# feeder_microcontroller_side.net
KiCad netlist of a schematic drawn in EAGLE
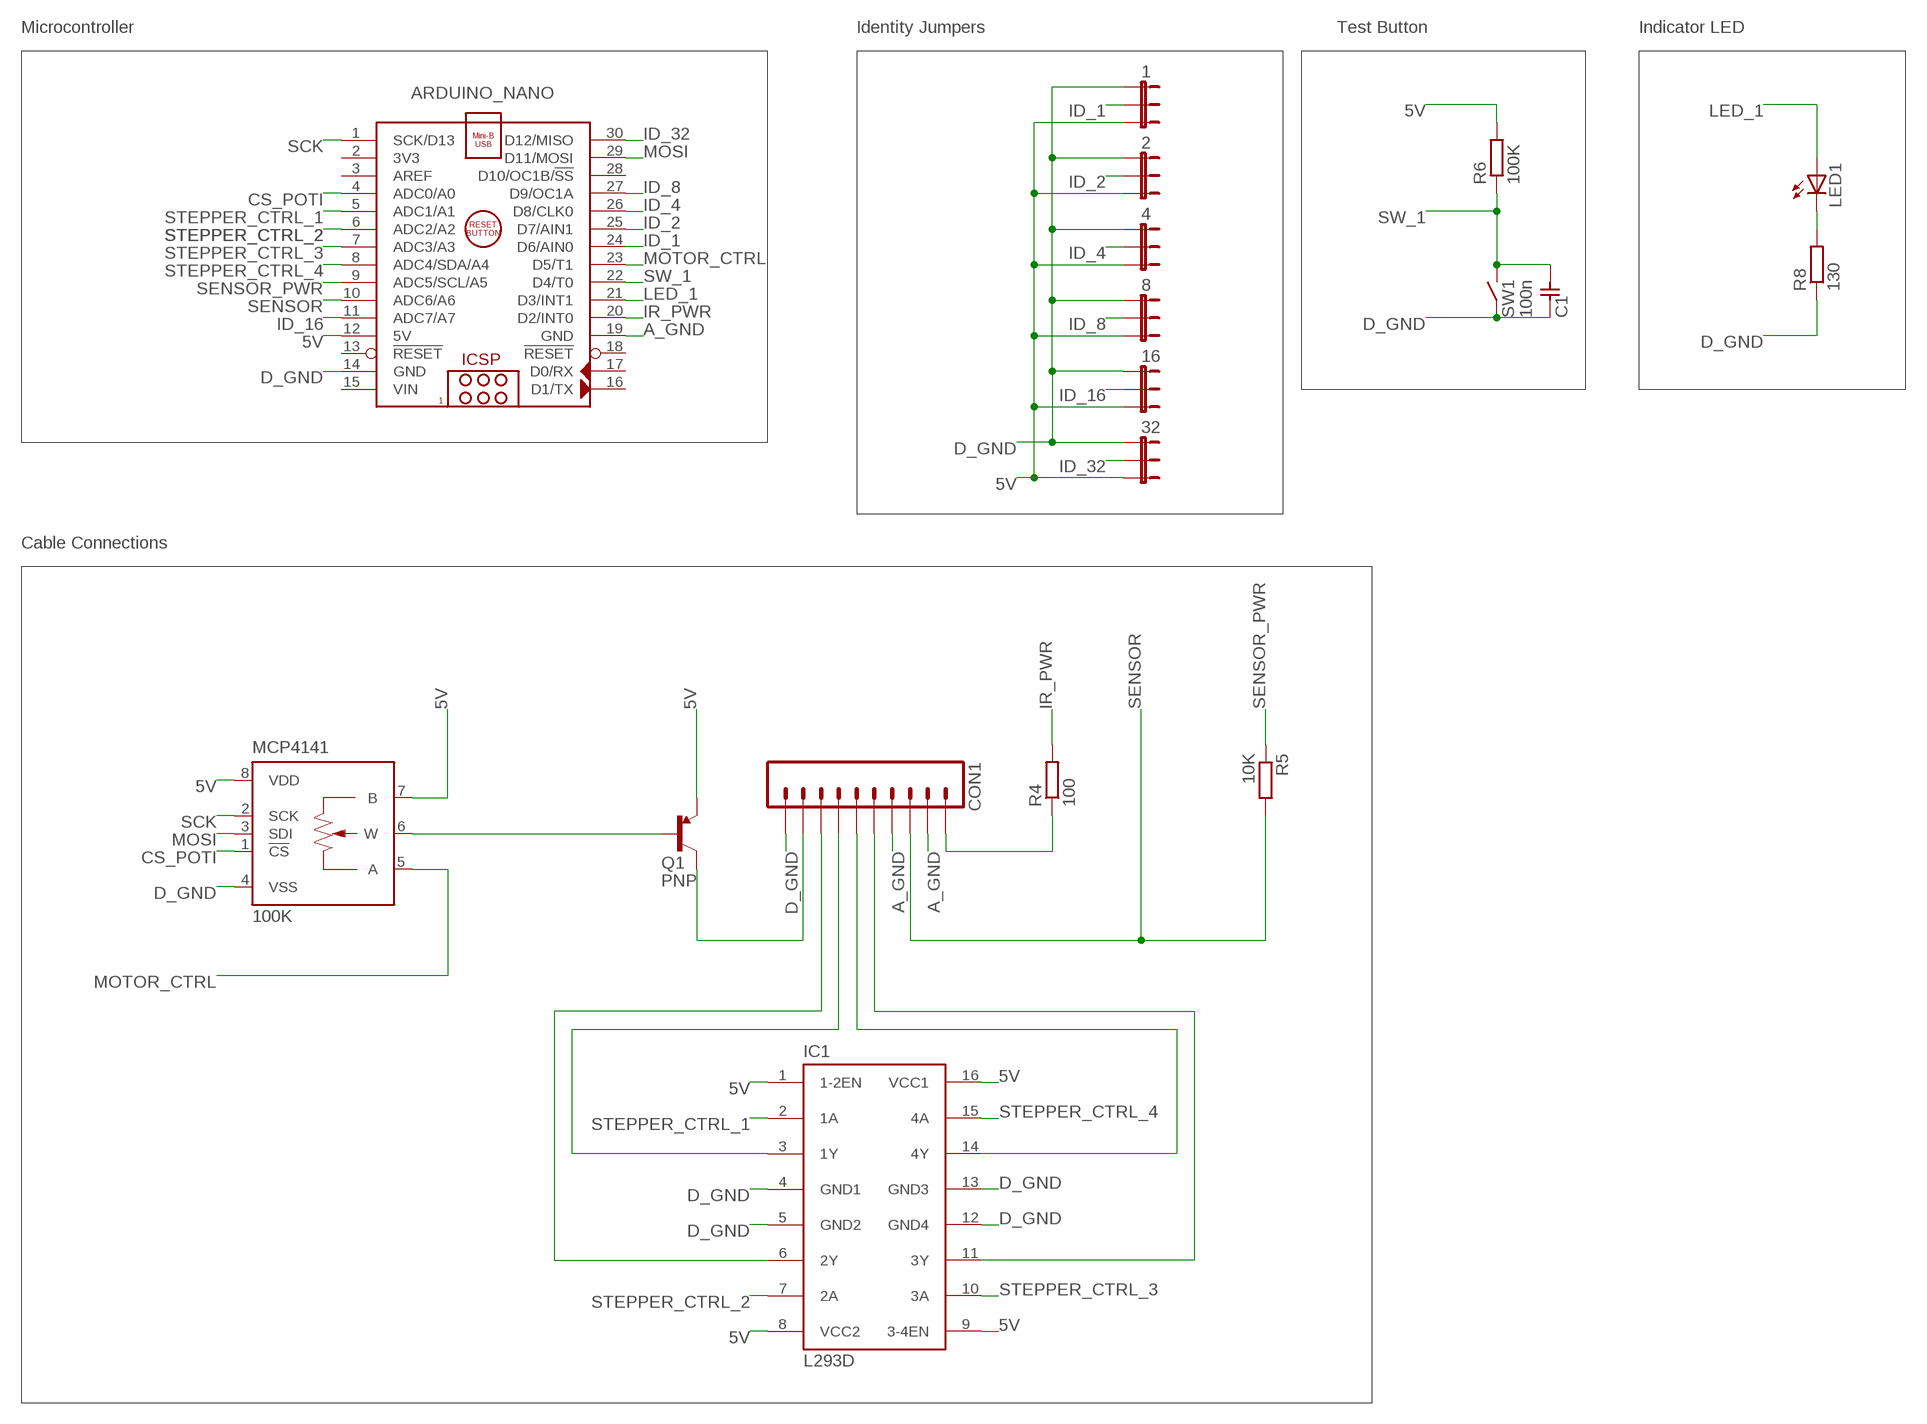
[diagram p0: schematic, sheet 1]

(export (version "E")
  (design (tool "Eeschema 10.0.6"))
  (components
    (comp (ref "1")
      (value "JP2E")
      (footprint "eagle-import:JP2")
      (libsource (lib "eagle-import") (part "JP2E"))
    )
    (comp (ref "2")
      (value "JP2E")
      (footprint "eagle-import:JP2")
      (libsource (lib "eagle-import") (part "JP2E"))
    )
    (comp (ref "4")
      (value "JP2E")
      (footprint "eagle-import:JP2")
      (libsource (lib "eagle-import") (part "JP2E"))
    )
    (comp (ref "8")
      (value "JP2E")
      (footprint "eagle-import:JP2")
      (libsource (lib "eagle-import") (part "JP2E"))
    )
    (comp (ref "16")
      (value "JP2E")
      (footprint "eagle-import:JP2")
      (libsource (lib "eagle-import") (part "JP2E"))
    )
    (comp (ref "32")
      (value "JP2E")
      (footprint "eagle-import:JP2")
      (libsource (lib "eagle-import") (part "JP2E"))
    )
    (comp (ref "ARDUINO_NANO")
      (value "ARDUINO_NANO")
      (footprint "eagle-import:ARDUINO_NANO")
      (libsource (lib "eagle-import") (part "ARDUINO_NANO"))
    )
    (comp (ref "C1")
      (value "100n")
      (footprint "eagle-import:CAPACITOR")
      (libsource (lib "eagle-import") (part "CAPACITOR"))
    )
    (comp (ref "CON1")
      (value "CON_10")
      (footprint "eagle-import:CON_10P_1.25_ALIEXPRESS")
      (libsource (lib "eagle-import") (part "CON_10"))
    )
    (comp (ref "IC1")
      (value "L293D")
      (footprint "eagle-import:DIL16")
      (libsource (lib "eagle-import") (part "L293D"))
    )
    (comp (ref "LED1")
      (value "LED_3MM")
      (footprint "eagle-import:TCR5000_IR_EMITTER")
      (libsource (lib "eagle-import") (part "LED_3MM"))
    )
    (comp (ref "MCP4141")
      (value "100K")
      (footprint "eagle-import:DIL08")
      (libsource (lib "eagle-import") (part "MCP_41X1_DIGI_POT"))
    )
    (comp (ref "Q1")
      (value "PNP")
      (footprint "eagle-import:TO92-")
      (libsource (lib "eagle-import") (part "PNP"))
    )
    (comp (ref "R4")
      (value "100")
      (footprint "eagle-import:0204_7")
      (libsource (lib "eagle-import") (part "R-EU_0204/7"))
    )
    (comp (ref "R5")
      (value "10K")
      (footprint "eagle-import:0204_7")
      (libsource (lib "eagle-import") (part "R-EU_0204/7"))
    )
    (comp (ref "R6")
      (value "100K")
      (footprint "eagle-import:0204_7")
      (libsource (lib "eagle-import") (part "R-EU_0204/7"))
    )
    (comp (ref "R8")
      (value "130")
      (footprint "eagle-import:0204_7")
      (libsource (lib "eagle-import") (part "R-EU_0204/7"))
    )
    (comp (ref "SW1")
      (value "BUTTON")
      (footprint "eagle-import:KS-01Q-01_BUTTON")
      (libsource (lib "eagle-import") (part "BUTTON"))
    )
  )
  (nets
    (net (code "1") (name "/5V") (class "Default")
      (node (ref "1") (pin "3") (pinfunction "3_3") (pintype "passive"))
      (node (ref "16") (pin "3") (pinfunction "3_3") (pintype "passive"))
      (node (ref "2") (pin "3") (pinfunction "3_3") (pintype "passive"))
      (node (ref "32") (pin "3") (pinfunction "3_3") (pintype "passive"))
      (node (ref "4") (pin "3") (pinfunction "3_3") (pintype "passive"))
      (node (ref "8") (pin "3") (pinfunction "3_3") (pintype "passive"))
      (node (ref "ARDUINO_NANO") (pin "12") (pinfunction "5V_12") (pintype "power_in"))
      (node (ref "IC1") (pin "1") (pinfunction "1-2EN_1") (pintype "input"))
      (node (ref "IC1") (pin "16") (pinfunction "VCC1_16") (pintype "power_in"))
      (node (ref "IC1") (pin "8") (pinfunction "VCC2_8") (pintype "power_in"))
      (node (ref "IC1") (pin "9") (pinfunction "3-4EN_9") (pintype "input"))
      (node (ref "MCP4141") (pin "7") (pinfunction "B_7") (pintype "passive"))
      (node (ref "MCP4141") (pin "8") (pinfunction "VDD_8") (pintype "power_in"))
      (node (ref "Q1") (pin "E") (pinfunction "E_E") (pintype "passive"))
      (node (ref "R6") (pin "2") (pinfunction "2_2") (pintype "passive"))
    )
    (net (code "2") (name "/A_GND") (class "Default")
      (node (ref "ARDUINO_NANO") (pin "19") (pinfunction "GND_19") (pintype "power_in"))
      (node (ref "CON1") (pin "2") (pinfunction "2_2") (pintype "passive"))
      (node (ref "CON1") (pin "4") (pinfunction "4_4") (pintype "passive"))
    )
    (net (code "3") (name "/CS_POTI") (class "Default")
      (node (ref "ARDUINO_NANO") (pin "4") (pinfunction "ADC0/A0_4") (pintype "bidirectional"))
      (node (ref "MCP4141") (pin "1") (pinfunction "~{CS}_1") (pintype "input"))
    )
    (net (code "4") (name "/D_GND") (class "Default")
      (node (ref "1") (pin "1") (pinfunction "1_1") (pintype "passive"))
      (node (ref "16") (pin "1") (pinfunction "1_1") (pintype "passive"))
      (node (ref "2") (pin "1") (pinfunction "1_1") (pintype "passive"))
      (node (ref "32") (pin "1") (pinfunction "1_1") (pintype "passive"))
      (node (ref "4") (pin "1") (pinfunction "1_1") (pintype "passive"))
      (node (ref "8") (pin "1") (pinfunction "1_1") (pintype "passive"))
      (node (ref "ARDUINO_NANO") (pin "14") (pinfunction "GND_14") (pintype "power_in"))
      (node (ref "C1") (pin "P$1") (pinfunction "1_P$1") (pintype "passive"))
      (node (ref "CON1") (pin "10") (pinfunction "10_10") (pintype "passive"))
      (node (ref "IC1") (pin "12") (pinfunction "GND4_12") (pintype "power_in"))
      (node (ref "IC1") (pin "13") (pinfunction "GND3_13") (pintype "power_in"))
      (node (ref "IC1") (pin "4") (pinfunction "GND1_4") (pintype "power_in"))
      (node (ref "IC1") (pin "5") (pinfunction "GND2_5") (pintype "power_in"))
      (node (ref "MCP4141") (pin "4") (pinfunction "VSS_4") (pintype "power_in"))
      (node (ref "R8") (pin "1") (pinfunction "1_1") (pintype "passive"))
      (node (ref "SW1") (pin "1") (pinfunction "1_1") (pintype "passive"))
      (node (ref "SW1") (pin "3") (pinfunction "1_3") (pintype "passive"))
    )
    (net (code "5") (name "/ID_1") (class "Default")
      (node (ref "1") (pin "2") (pinfunction "2_2") (pintype "passive"))
      (node (ref "ARDUINO_NANO") (pin "24") (pinfunction "D6/AIN0_24") (pintype "bidirectional"))
    )
    (net (code "6") (name "/ID_2") (class "Default")
      (node (ref "2") (pin "2") (pinfunction "2_2") (pintype "passive"))
      (node (ref "ARDUINO_NANO") (pin "25") (pinfunction "D7/AIN1_25") (pintype "bidirectional"))
    )
    (net (code "7") (name "/ID_4") (class "Default")
      (node (ref "4") (pin "2") (pinfunction "2_2") (pintype "passive"))
      (node (ref "ARDUINO_NANO") (pin "26") (pinfunction "D8/CLK0_26") (pintype "bidirectional"))
    )
    (net (code "8") (name "/ID_8") (class "Default")
      (node (ref "8") (pin "2") (pinfunction "2_2") (pintype "passive"))
      (node (ref "ARDUINO_NANO") (pin "27") (pinfunction "D9/OC1A_27") (pintype "bidirectional"))
    )
    (net (code "9") (name "/ID_16") (class "Default")
      (node (ref "16") (pin "2") (pinfunction "2_2") (pintype "passive"))
      (node (ref "ARDUINO_NANO") (pin "11") (pinfunction "ADC7/A7_11") (pintype "bidirectional"))
    )
    (net (code "10") (name "/ID_32") (class "Default")
      (node (ref "32") (pin "2") (pinfunction "2_2") (pintype "passive"))
      (node (ref "ARDUINO_NANO") (pin "30") (pinfunction "D12/MISO_30") (pintype "bidirectional"))
    )
    (net (code "11") (name "/IR_PWR") (class "Default")
      (node (ref "ARDUINO_NANO") (pin "20") (pinfunction "D2/INT0_20") (pintype "bidirectional"))
      (node (ref "R4") (pin "2") (pinfunction "2_2") (pintype "passive"))
    )
    (net (code "12") (name "/LED_1") (class "Default")
      (node (ref "ARDUINO_NANO") (pin "21") (pinfunction "D3/INT1_21") (pintype "bidirectional"))
      (node (ref "LED1") (pin "A") (pinfunction "A_A") (pintype "passive"))
    )
    (net (code "13") (name "/MOSI") (class "Default")
      (node (ref "ARDUINO_NANO") (pin "29") (pinfunction "D11/MOSI_29") (pintype "bidirectional"))
      (node (ref "MCP4141") (pin "3") (pinfunction "SDI_3") (pintype "input"))
    )
    (net (code "14") (name "/MOTOR_CTRL") (class "Default")
      (node (ref "ARDUINO_NANO") (pin "23") (pinfunction "D5/T1_23") (pintype "bidirectional"))
      (node (ref "MCP4141") (pin "5") (pinfunction "A_5") (pintype "passive"))
    )
    (net (code "15") (name "/SCK") (class "Default")
      (node (ref "ARDUINO_NANO") (pin "1") (pinfunction "SCK/D13_1") (pintype "bidirectional"))
      (node (ref "MCP4141") (pin "2") (pinfunction "SCK_2") (pintype "input"))
    )
    (net (code "16") (name "/SENSOR") (class "Default")
      (node (ref "ARDUINO_NANO") (pin "10") (pinfunction "ADC6/A6_10") (pintype "bidirectional"))
      (node (ref "CON1") (pin "3") (pinfunction "3_3") (pintype "passive"))
      (node (ref "R5") (pin "2") (pinfunction "2_2") (pintype "passive"))
    )
    (net (code "17") (name "/SENSOR_PWR") (class "Default")
      (node (ref "ARDUINO_NANO") (pin "9") (pinfunction "ADC5/SCL/A5_9") (pintype "bidirectional"))
      (node (ref "R5") (pin "1") (pinfunction "1_1") (pintype "passive"))
    )
    (net (code "18") (name "/STEPPER_CTRL_1") (class "Default")
      (node (ref "ARDUINO_NANO") (pin "5") (pinfunction "ADC1/A1_5") (pintype "bidirectional"))
      (node (ref "IC1") (pin "2") (pinfunction "1A_2") (pintype "input"))
    )
    (net (code "19") (name "/STEPPER_CTRL_2") (class "Default")
      (node (ref "ARDUINO_NANO") (pin "6") (pinfunction "ADC2/A2_6") (pintype "bidirectional"))
      (node (ref "IC1") (pin "7") (pinfunction "2A_7") (pintype "input"))
    )
    (net (code "20") (name "/STEPPER_CTRL_3") (class "Default")
      (node (ref "ARDUINO_NANO") (pin "7") (pinfunction "ADC3/A3_7") (pintype "bidirectional"))
      (node (ref "IC1") (pin "10") (pinfunction "3A_10") (pintype "input"))
    )
    (net (code "21") (name "/STEPPER_CTRL_4") (class "Default")
      (node (ref "ARDUINO_NANO") (pin "8") (pinfunction "ADC4/SDA/A4_8") (pintype "bidirectional"))
      (node (ref "IC1") (pin "15") (pinfunction "4A_15") (pintype "input"))
    )
    (net (code "22") (name "/SW_1") (class "Default")
      (node (ref "ARDUINO_NANO") (pin "22") (pinfunction "D4/T0_22") (pintype "bidirectional"))
      (node (ref "C1") (pin "P$2") (pinfunction "2_P$2") (pintype "passive"))
      (node (ref "R6") (pin "1") (pinfunction "1_1") (pintype "passive"))
      (node (ref "SW1") (pin "2") (pinfunction "2_2") (pintype "passive"))
      (node (ref "SW1") (pin "4") (pinfunction "2_4") (pintype "passive"))
    )
    (net (code "23") (name "/VIN") (class "Default")
      (node (ref "ARDUINO_NANO") (pin "15") (pinfunction "VIN_15") (pintype "power_in"))
    )
    (net (code "24") (name "Net-(CON1-Pad1)") (class "Default")
      (node (ref "CON1") (pin "1") (pinfunction "1_1") (pintype "passive"))
      (node (ref "R4") (pin "1") (pinfunction "1_1") (pintype "passive"))
    )
    (net (code "25") (name "Net-(CON1-Pad9)") (class "Default")
      (node (ref "CON1") (pin "9") (pinfunction "9_9") (pintype "passive"))
      (node (ref "Q1") (pin "C") (pinfunction "C_C") (pintype "passive"))
    )
    (net (code "26") (name "Net-(IC1-1Y)") (class "Default")
      (node (ref "CON1") (pin "7") (pinfunction "7_7") (pintype "passive"))
      (node (ref "IC1") (pin "3") (pinfunction "1Y_3") (pintype "output"))
    )
    (net (code "27") (name "Net-(IC1-2Y)") (class "Default")
      (node (ref "CON1") (pin "8") (pinfunction "8_8") (pintype "passive"))
      (node (ref "IC1") (pin "6") (pinfunction "2Y_6") (pintype "output"))
    )
    (net (code "28") (name "Net-(IC1-3Y)") (class "Default")
      (node (ref "CON1") (pin "5") (pinfunction "5_5") (pintype "passive"))
      (node (ref "IC1") (pin "11") (pinfunction "3Y_11") (pintype "output"))
    )
    (net (code "29") (name "Net-(IC1-4Y)") (class "Default")
      (node (ref "CON1") (pin "6") (pinfunction "6_6") (pintype "passive"))
      (node (ref "IC1") (pin "14") (pinfunction "4Y_14") (pintype "output"))
    )
    (net (code "30") (name "Net-(LED1-PadC)") (class "Default")
      (node (ref "LED1") (pin "C") (pinfunction "C_C") (pintype "passive"))
      (node (ref "R8") (pin "2") (pinfunction "2_2") (pintype "passive"))
    )
    (net (code "31") (name "Net-(MCP4141-W)") (class "Default")
      (node (ref "MCP4141") (pin "6") (pinfunction "W_6") (pintype "passive"))
      (node (ref "Q1") (pin "B") (pinfunction "B_B") (pintype "passive"))
    )
    (net (code "32") (name "unconnected-(ARDUINO_NANO-3V3-Pad2)") (class "Default")
      (node (ref "ARDUINO_NANO") (pin "2") (pinfunction "3V3_2") (pintype "output"))
    )
    (net (code "33") (name "unconnected-(ARDUINO_NANO-AREF-Pad3)") (class "Default")
      (node (ref "ARDUINO_NANO") (pin "3") (pinfunction "AREF_3") (pintype "input"))
    )
    (net (code "34") (name "unconnected-(ARDUINO_NANO-D0{slash}RX-Pad17)") (class "Default")
      (node (ref "ARDUINO_NANO") (pin "17") (pinfunction "D0/RX_17") (pintype "bidirectional"))
    )
    (net (code "35") (name "unconnected-(ARDUINO_NANO-D1{slash}TX-Pad16)") (class "Default")
      (node (ref "ARDUINO_NANO") (pin "16") (pinfunction "D1/TX_16") (pintype "bidirectional"))
    )
    (net (code "36") (name "unconnected-(ARDUINO_NANO-D10{slash}OC1B{slash}~{SS}-Pad28)") (class "Default")
      (node (ref "ARDUINO_NANO") (pin "28") (pinfunction "D10/OC1B/~{SS}_28") (pintype "bidirectional"))
    )
    (net (code "37") (name "unconnected-(ARDUINO_NANO-~{RESET}-Pad13)") (class "Default")
      (node (ref "ARDUINO_NANO") (pin "13") (pinfunction "~{RESET}_13") (pintype "input"))
    )
    (net (code "38") (name "unconnected-(ARDUINO_NANO-~{RESET}-Pad18)") (class "Default")
      (node (ref "ARDUINO_NANO") (pin "18") (pinfunction "~{RESET}_18") (pintype "input"))
    )
  )
)
